# SCH_MagControl_Sheet2.net
KiCad netlist of a schematic drawn in Altium Designer
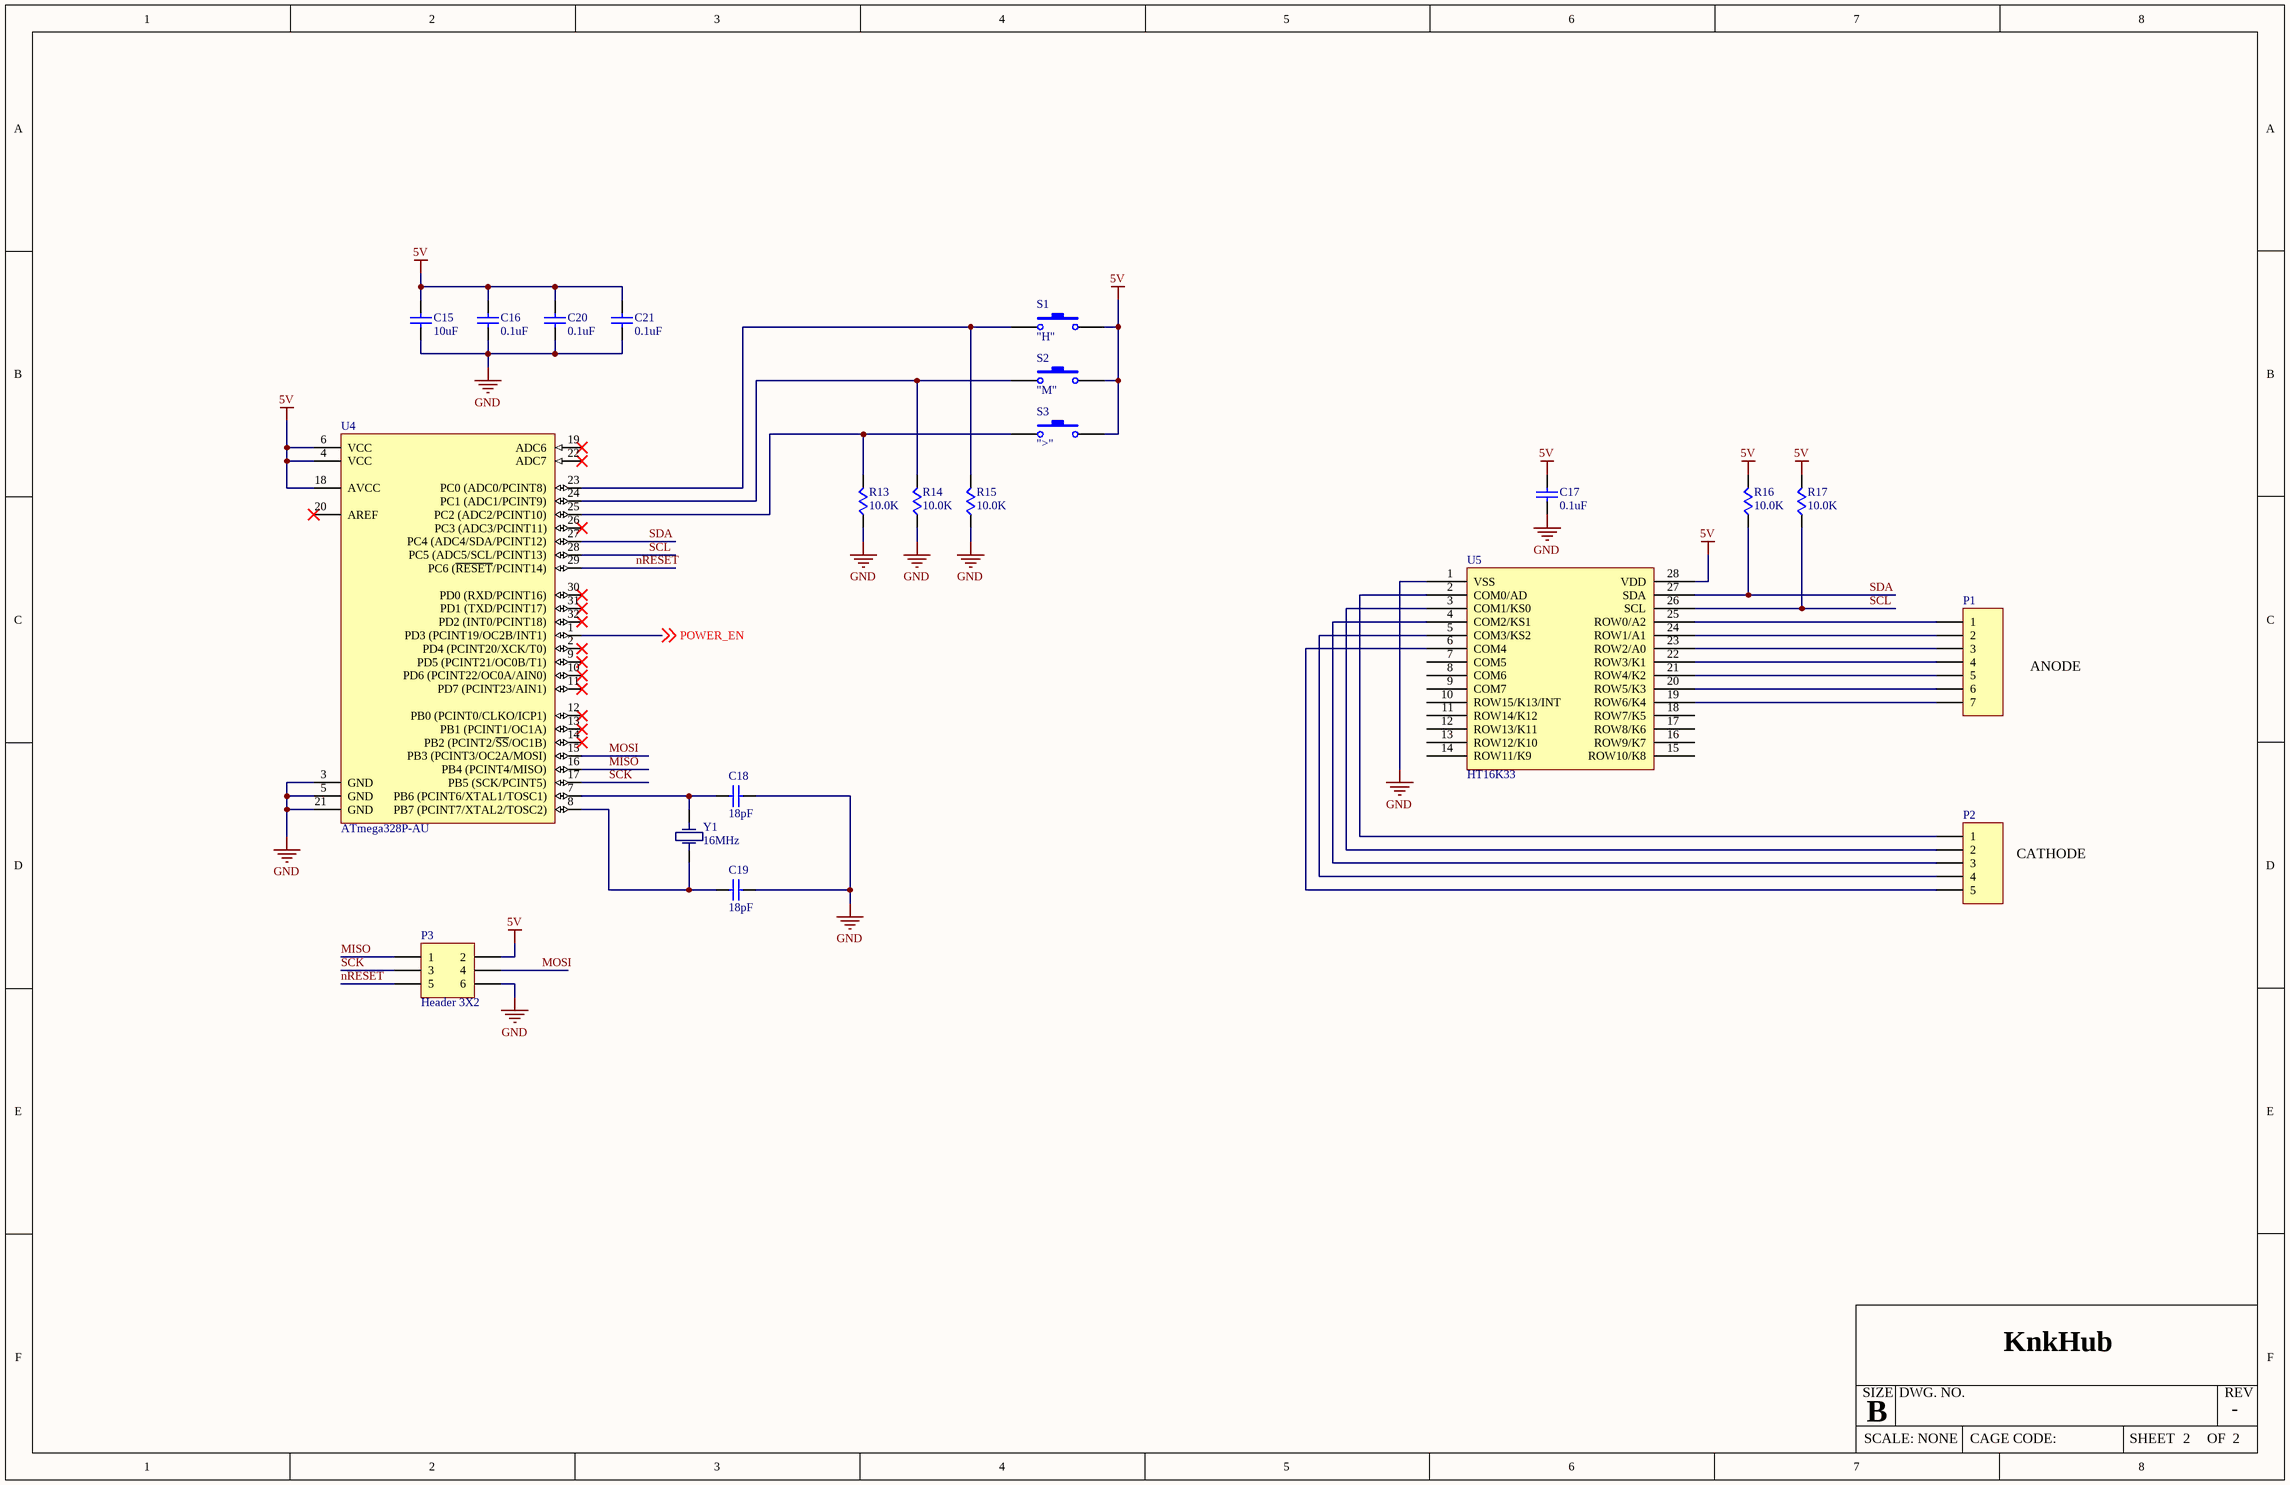
[diagram p0: SCH_MagControl_Sheet2.SchDoc]

(export (version "E")
  (design (tool "Eeschema 10.0.6"))
  (components
    (comp (ref "C15")
      (value "10uF")
      (footprint "CAPC1608L")
      (description "Capacitor (SMD)")
      (fields (field (name "TOLERANCE") "20%") (field (name "VOLTAGE") "6.3V"))
      (libsource (lib "MAST_Library") (part "Cap Semi"))
    )
    (comp (ref "C16")
      (value "0.1uF")
      (footprint "CAPC1005L")
      (description "Capacitor (SMD)")
      (fields (field (name "TOLERANCE") "20%"))
      (libsource (lib "MAST_Library") (part "Cap Semi"))
    )
    (comp (ref "C17")
      (value "0.1uF")
      (footprint "CAPC1005L")
      (description "Capacitor (SMD)")
      (fields (field (name "TOLERANCE") "20%"))
      (libsource (lib "MAST_Library") (part "Cap Semi"))
    )
    (comp (ref "C18")
      (value "18pF")
      (footprint "CAPC1005L")
      (description "Capacitor (SMD)")
      (fields
        (field (name "TOLERANCE") "5%")
        (field (name "VOLTAGE") "50V")
        (field (name "PUBLISHER") "Altium Limited")
      )
      (libsource (lib "HCG_Library") (part "Cap Semi"))
    )
    (comp (ref "C19")
      (value "18pF")
      (footprint "CAPC1005L")
      (description "Capacitor (SMD)")
      (fields
        (field (name "TOLERANCE") "5%")
        (field (name "VOLTAGE") "50V")
        (field (name "PUBLISHER") "Altium Limited")
      )
      (libsource (lib "HCG_Library") (part "Cap Semi"))
    )
    (comp (ref "C20")
      (value "0.1uF")
      (footprint "CAPC1005L")
      (description "Capacitor (SMD)")
      (fields (field (name "TOLERANCE") "20%"))
      (libsource (lib "MAST_Library") (part "Cap Semi"))
    )
    (comp (ref "C21")
      (value "0.1uF")
      (footprint "CAPC1005L")
      (description "Capacitor (SMD)")
      (fields (field (name "TOLERANCE") "20%"))
      (libsource (lib "MAST_Library") (part "Cap Semi"))
    )
    (comp (ref "P1")
      (value "~")
      (footprint "HDR1X7")
      (description "Header, 7-Pin")
      (fields (field (name "PUBLISHER") "Altium Limited"))
      (libsource (lib "Miscellaneous Connectors") (part "Header 7"))
    )
    (comp (ref "P2")
      (value "~")
      (footprint "HDR1X5")
      (description "Header, 5-Pin")
      (fields (field (name "PUBLISHER") "Altium Limited"))
      (libsource (lib "Miscellaneous Connectors") (part "Header 5"))
    )
    (comp (ref "P3")
      (value "Header 3X2")
      (footprint "HDR2X3")
      (description "Header, 3-Pin, Dual row")
      (fields (field (name "PUBLISHER") "Altium Limited"))
      (libsource (lib "Miscellaneous Connectors") (part "Header 3X2"))
    )
    (comp (ref "R13")
      (value "10.0K")
      (footprint "RESC1005N")
      (description "RES 10.0K OHM 1/10W 1% 0402 SMD")
      (fields (field (name "TOLERANCE") "1%"))
      (libsource (lib "MAST_Library") (part "R"))
    )
    (comp (ref "R14")
      (value "10.0K")
      (footprint "RESC1005N")
      (description "RES 10.0K OHM 1/10W 1% 0402 SMD")
      (fields (field (name "TOLERANCE") "1%"))
      (libsource (lib "MAST_Library") (part "R"))
    )
    (comp (ref "R15")
      (value "10.0K")
      (footprint "RESC1005N")
      (description "RES 10.0K OHM 1/10W 1% 0402 SMD")
      (fields (field (name "TOLERANCE") "1%"))
      (libsource (lib "MAST_Library") (part "R"))
    )
    (comp (ref "R16")
      (value "10.0K")
      (footprint "RESC1005N")
      (description "RES 10.0K OHM 1/10W 1% 0402 SMD")
      (fields (field (name "TOLERANCE") "1%"))
      (libsource (lib "MAST_Library") (part "R"))
    )
    (comp (ref "R17")
      (value "10.0K")
      (footprint "RESC1005N")
      (description "RES 10.0K OHM 1/10W 1% 0402 SMD")
      (fields (field (name "TOLERANCE") "1%"))
      (libsource (lib "MAST_Library") (part "R"))
    )
    (comp (ref "S1")
      (value "\"H\"")
      (footprint "SPST-2")
      (description "Switch")
      (fields (field (name "PUBLISHER") "Altium Limited"))
      (libsource (lib "Miscellaneous Devices") (part "SW-PB"))
    )
    (comp (ref "S2")
      (value "\"M\"")
      (footprint "SPST-2")
      (description "Switch")
      (fields (field (name "PUBLISHER") "Altium Limited"))
      (libsource (lib "Miscellaneous Devices") (part "SW-PB"))
    )
    (comp (ref "S3")
      (value "\">\"")
      (footprint "SPST-2")
      (description "Switch")
      (fields (field (name "PUBLISHER") "Altium Limited"))
      (libsource (lib "Miscellaneous Devices") (part "SW-PB"))
    )
    (comp (ref "U4")
      (value "ATmega328P-AU")
      (footprint "32A_L")
      (libsource (lib "Altium Content Vault") (part "MC-8B-ATM48-SQ32"))
    )
    (comp (ref "U5")
      (value "HT16K33")
      (footprint "SOP127P1030X264-28N")
      (description "LED Matrix Driver")
      (libsource (lib "HCG_Library") (part "HT16K33_28"))
    )
    (comp (ref "Y1")
      (value "16MHz")
      (footprint "CSM-3X")
      (description "CRYSTAL")
      (fields (field (name "TOLERANCE") "30ppm"))
      (libsource (lib "HCG_Library") (part "CRYSTAL"))
    )
  )
  (nets
    (net (code "1") (name "/MISO") (class "Default")
      (node (ref "P3") (pin "1") (pinfunction "1_1") (pintype "passive"))
      (node (ref "U4") (pin "16") (pinfunction "PB4_(PCINT4/MISO)_16") (pintype "bidirectional"))
    )
    (net (code "2") (name "/MOSI") (class "Default")
      (node (ref "P3") (pin "4") (pinfunction "4_4") (pintype "passive"))
      (node (ref "U4") (pin "15") (pinfunction "PB3_(PCINT3/OC2A/MOSI)_15") (pintype "bidirectional"))
    )
    (net (code "3") (name "/SCK") (class "Default")
      (node (ref "P3") (pin "3") (pinfunction "3_3") (pintype "passive"))
      (node (ref "U4") (pin "17") (pinfunction "PB5_(SCK/PCINT5)_17") (pintype "bidirectional"))
    )
    (net (code "4") (name "/SCL") (class "Default")
      (node (ref "R17") (pin "1") (pinfunction "1_1") (pintype "passive"))
      (node (ref "U4") (pin "28") (pinfunction "PC5_(ADC5/SCL/PCINT13)_28") (pintype "bidirectional"))
      (node (ref "U5") (pin "26") (pinfunction "SCL_26") (pintype "passive"))
    )
    (net (code "5") (name "/SDA") (class "Default")
      (node (ref "R16") (pin "1") (pinfunction "1_1") (pintype "passive"))
      (node (ref "U4") (pin "27") (pinfunction "PC4_(ADC4/SDA/PCINT12)_27") (pintype "bidirectional"))
      (node (ref "U5") (pin "27") (pinfunction "SDA_27") (pintype "passive"))
    )
    (net (code "6") (name "/nRESET") (class "Default")
      (node (ref "P3") (pin "5") (pinfunction "5_5") (pintype "passive"))
      (node (ref "U4") (pin "29") (pinfunction "PC6_(~{RESET}/PCINT14)_29") (pintype "bidirectional"))
    )
    (net (code "7") (name "5V") (class "Default")
      (node (ref "C15") (pin "2") (pinfunction "2_2") (pintype "passive"))
      (node (ref "C16") (pin "2") (pinfunction "2_2") (pintype "passive"))
      (node (ref "C17") (pin "2") (pinfunction "2_2") (pintype "passive"))
      (node (ref "C20") (pin "2") (pinfunction "2_2") (pintype "passive"))
      (node (ref "C21") (pin "2") (pinfunction "2_2") (pintype "passive"))
      (node (ref "P3") (pin "2") (pinfunction "2_2") (pintype "passive"))
      (node (ref "R16") (pin "2") (pinfunction "2_2") (pintype "passive"))
      (node (ref "R17") (pin "2") (pinfunction "2_2") (pintype "passive"))
      (node (ref "S1") (pin "2") (pinfunction "2_2") (pintype "passive"))
      (node (ref "S2") (pin "2") (pinfunction "2_2") (pintype "passive"))
      (node (ref "S3") (pin "2") (pinfunction "2_2") (pintype "passive"))
      (node (ref "U4") (pin "18") (pinfunction "AVCC_18") (pintype "power_in"))
      (node (ref "U4") (pin "4") (pinfunction "VCC_4") (pintype "power_in"))
      (node (ref "U4") (pin "6") (pinfunction "VCC_6") (pintype "power_in"))
      (node (ref "U5") (pin "28") (pinfunction "VDD_28") (pintype "passive"))
    )
    (net (code "8") (name "GND") (class "Default")
      (node (ref "C15") (pin "1") (pinfunction "1_1") (pintype "passive"))
      (node (ref "C16") (pin "1") (pinfunction "1_1") (pintype "passive"))
      (node (ref "C17") (pin "1") (pinfunction "1_1") (pintype "passive"))
      (node (ref "C18") (pin "1") (pinfunction "1_1") (pintype "passive"))
      (node (ref "C19") (pin "1") (pinfunction "1_1") (pintype "passive"))
      (node (ref "C20") (pin "1") (pinfunction "1_1") (pintype "passive"))
      (node (ref "C21") (pin "1") (pinfunction "1_1") (pintype "passive"))
      (node (ref "P3") (pin "6") (pinfunction "6_6") (pintype "passive"))
      (node (ref "R13") (pin "1") (pinfunction "1_1") (pintype "passive"))
      (node (ref "R14") (pin "1") (pinfunction "1_1") (pintype "passive"))
      (node (ref "R15") (pin "1") (pinfunction "1_1") (pintype "passive"))
      (node (ref "U4") (pin "21") (pinfunction "GND_21") (pintype "power_in"))
      (node (ref "U4") (pin "3") (pinfunction "GND_3") (pintype "power_in"))
      (node (ref "U4") (pin "5") (pinfunction "GND_5") (pintype "power_in"))
      (node (ref "U5") (pin "1") (pinfunction "VSS_1") (pintype "passive"))
    )
    (net (code "9") (name "Net-(U4-PB6_(PCINT6{slash}XTAL1{slash}TOSC1))") (class "Default")
      (node (ref "C18") (pin "2") (pinfunction "2_2") (pintype "passive"))
      (node (ref "U4") (pin "7") (pinfunction "PB6_(PCINT6/XTAL1/TOSC1)_7") (pintype "bidirectional"))
      (node (ref "Y1") (pin "1") (pinfunction "CI_1") (pintype "passive"))
    )
    (net (code "10") (name "Net-(U4-PB7_(PCINT7{slash}XTAL2{slash}TOSC2))") (class "Default")
      (node (ref "C19") (pin "2") (pinfunction "2_2") (pintype "passive"))
      (node (ref "U4") (pin "8") (pinfunction "PB7_(PCINT7/XTAL2/TOSC2)_8") (pintype "bidirectional"))
      (node (ref "Y1") (pin "2") (pinfunction "CO_2") (pintype "passive"))
    )
    (net (code "11") (name "Net-(U4-PC0_(ADC0{slash}PCINT8))") (class "Default")
      (node (ref "R15") (pin "2") (pinfunction "2_2") (pintype "passive"))
      (node (ref "S1") (pin "1") (pinfunction "1_1") (pintype "passive"))
      (node (ref "U4") (pin "23") (pinfunction "PC0_(ADC0/PCINT8)_23") (pintype "bidirectional"))
    )
    (net (code "12") (name "Net-(U4-PC1_(ADC1{slash}PCINT9))") (class "Default")
      (node (ref "R14") (pin "2") (pinfunction "2_2") (pintype "passive"))
      (node (ref "S2") (pin "1") (pinfunction "1_1") (pintype "passive"))
      (node (ref "U4") (pin "24") (pinfunction "PC1_(ADC1/PCINT9)_24") (pintype "bidirectional"))
    )
    (net (code "13") (name "Net-(U4-PC2_(ADC2{slash}PCINT10))") (class "Default")
      (node (ref "R13") (pin "2") (pinfunction "2_2") (pintype "passive"))
      (node (ref "S3") (pin "1") (pinfunction "1_1") (pintype "passive"))
      (node (ref "U4") (pin "25") (pinfunction "PC2_(ADC2/PCINT10)_25") (pintype "bidirectional"))
    )
    (net (code "14") (name "Net-(U5-COM0{slash}AD)") (class "Default")
      (node (ref "P2") (pin "1") (pinfunction "1_1") (pintype "passive"))
      (node (ref "U5") (pin "2") (pinfunction "COM0/AD_2") (pintype "passive"))
    )
    (net (code "15") (name "Net-(U5-COM1{slash}KS0)") (class "Default")
      (node (ref "P2") (pin "2") (pinfunction "2_2") (pintype "passive"))
      (node (ref "U5") (pin "3") (pinfunction "COM1/KS0_3") (pintype "passive"))
    )
    (net (code "16") (name "Net-(U5-COM2{slash}KS1)") (class "Default")
      (node (ref "P2") (pin "3") (pinfunction "3_3") (pintype "passive"))
      (node (ref "U5") (pin "4") (pinfunction "COM2/KS1_4") (pintype "passive"))
    )
    (net (code "17") (name "Net-(U5-COM3{slash}KS2)") (class "Default")
      (node (ref "P2") (pin "4") (pinfunction "4_4") (pintype "passive"))
      (node (ref "U5") (pin "5") (pinfunction "COM3/KS2_5") (pintype "passive"))
    )
    (net (code "18") (name "Net-(U5-COM4)") (class "Default")
      (node (ref "P2") (pin "5") (pinfunction "5_5") (pintype "passive"))
      (node (ref "U5") (pin "6") (pinfunction "COM4_6") (pintype "passive"))
    )
    (net (code "19") (name "Net-(U5-ROW0{slash}A2)") (class "Default")
      (node (ref "P1") (pin "1") (pinfunction "1_1") (pintype "passive"))
      (node (ref "U5") (pin "25") (pinfunction "ROW0/A2_25") (pintype "passive"))
    )
    (net (code "20") (name "Net-(U5-ROW1{slash}A1)") (class "Default")
      (node (ref "P1") (pin "2") (pinfunction "2_2") (pintype "passive"))
      (node (ref "U5") (pin "24") (pinfunction "ROW1/A1_24") (pintype "passive"))
    )
    (net (code "21") (name "Net-(U5-ROW2{slash}A0)") (class "Default")
      (node (ref "P1") (pin "3") (pinfunction "3_3") (pintype "passive"))
      (node (ref "U5") (pin "23") (pinfunction "ROW2/A0_23") (pintype "passive"))
    )
    (net (code "22") (name "Net-(U5-ROW3{slash}K1)") (class "Default")
      (node (ref "P1") (pin "4") (pinfunction "4_4") (pintype "passive"))
      (node (ref "U5") (pin "22") (pinfunction "ROW3/K1_22") (pintype "passive"))
    )
    (net (code "23") (name "Net-(U5-ROW4{slash}K2)") (class "Default")
      (node (ref "P1") (pin "5") (pinfunction "5_5") (pintype "passive"))
      (node (ref "U5") (pin "21") (pinfunction "ROW4/K2_21") (pintype "passive"))
    )
    (net (code "24") (name "Net-(U5-ROW5{slash}K3)") (class "Default")
      (node (ref "P1") (pin "6") (pinfunction "6_6") (pintype "passive"))
      (node (ref "U5") (pin "20") (pinfunction "ROW5/K3_20") (pintype "passive"))
    )
    (net (code "25") (name "Net-(U5-ROW6{slash}K4)") (class "Default")
      (node (ref "P1") (pin "7") (pinfunction "7_7") (pintype "passive"))
      (node (ref "U5") (pin "19") (pinfunction "ROW6/K4_19") (pintype "passive"))
    )
    (net (code "26") (name "POWER_EN") (class "Default")
      (node (ref "U4") (pin "1") (pinfunction "PD3_(PCINT19/OC2B/INT1)_1") (pintype "bidirectional"))
    )
    (net (code "27") (name "unconnected-(U4-ADC6-Pad19)") (class "Default")
      (node (ref "U4") (pin "19") (pinfunction "ADC6_19") (pintype "input+no_connect"))
    )
    (net (code "28") (name "unconnected-(U4-ADC7-Pad22)") (class "Default")
      (node (ref "U4") (pin "22") (pinfunction "ADC7_22") (pintype "input+no_connect"))
    )
    (net (code "29") (name "unconnected-(U4-AREF-Pad20)") (class "Default")
      (node (ref "U4") (pin "20") (pinfunction "AREF_20") (pintype "passive+no_connect"))
    )
    (net (code "30") (name "unconnected-(U4-PB0_(PCINT0{slash}CLKO{slash}ICP1)-Pad12)") (class "Default")
      (node (ref "U4") (pin "12") (pinfunction "PB0_(PCINT0/CLKO/ICP1)_12") (pintype "bidirectional+no_connect"))
    )
    (net (code "31") (name "unconnected-(U4-PB1_(PCINT1{slash}OC1A)-Pad13)") (class "Default")
      (node (ref "U4") (pin "13") (pinfunction "PB1_(PCINT1/OC1A)_13") (pintype "bidirectional+no_connect"))
    )
    (net (code "32") (name "unconnected-(U4-PB2_(PCINT2{slash}~{SS}{slash}OC1B)-Pad14)") (class "Default")
      (node (ref "U4") (pin "14") (pinfunction "PB2_(PCINT2/~{SS}/OC1B)_14") (pintype "bidirectional+no_connect"))
    )
    (net (code "33") (name "unconnected-(U4-PC3_(ADC3{slash}PCINT11)-Pad26)") (class "Default")
      (node (ref "U4") (pin "26") (pinfunction "PC3_(ADC3/PCINT11)_26") (pintype "bidirectional+no_connect"))
    )
    (net (code "34") (name "unconnected-(U4-PD0_(RXD{slash}PCINT16)-Pad30)") (class "Default")
      (node (ref "U4") (pin "30") (pinfunction "PD0_(RXD/PCINT16)_30") (pintype "bidirectional+no_connect"))
    )
    (net (code "35") (name "unconnected-(U4-PD1_(TXD{slash}PCINT17)-Pad31)") (class "Default")
      (node (ref "U4") (pin "31") (pinfunction "PD1_(TXD/PCINT17)_31") (pintype "bidirectional+no_connect"))
    )
    (net (code "36") (name "unconnected-(U4-PD2_(INT0{slash}PCINT18)-Pad32)") (class "Default")
      (node (ref "U4") (pin "32") (pinfunction "PD2_(INT0/PCINT18)_32") (pintype "bidirectional+no_connect"))
    )
    (net (code "37") (name "unconnected-(U4-PD4_(PCINT20{slash}XCK{slash}T0)-Pad2)") (class "Default")
      (node (ref "U4") (pin "2") (pinfunction "PD4_(PCINT20/XCK/T0)_2") (pintype "bidirectional+no_connect"))
    )
    (net (code "38") (name "unconnected-(U4-PD5_(PCINT21{slash}OC0B{slash}T1)-Pad9)") (class "Default")
      (node (ref "U4") (pin "9") (pinfunction "PD5_(PCINT21/OC0B/T1)_9") (pintype "bidirectional+no_connect"))
    )
    (net (code "39") (name "unconnected-(U4-PD6_(PCINT22{slash}OC0A{slash}AIN0)-Pad10)") (class "Default")
      (node (ref "U4") (pin "10") (pinfunction "PD6_(PCINT22/OC0A/AIN0)_10") (pintype "bidirectional+no_connect"))
    )
    (net (code "40") (name "unconnected-(U4-PD7_(PCINT23{slash}AIN1)-Pad11)") (class "Default")
      (node (ref "U4") (pin "11") (pinfunction "PD7_(PCINT23/AIN1)_11") (pintype "bidirectional+no_connect"))
    )
    (net (code "41") (name "unconnected-(U5-COM5-Pad7)") (class "Default")
      (node (ref "U5") (pin "7") (pinfunction "COM5_7") (pintype "passive"))
    )
    (net (code "42") (name "unconnected-(U5-COM6-Pad8)") (class "Default")
      (node (ref "U5") (pin "8") (pinfunction "COM6_8") (pintype "passive"))
    )
    (net (code "43") (name "unconnected-(U5-COM7-Pad9)") (class "Default")
      (node (ref "U5") (pin "9") (pinfunction "COM7_9") (pintype "passive"))
    )
    (net (code "44") (name "unconnected-(U5-ROW7{slash}K5-Pad18)") (class "Default")
      (node (ref "U5") (pin "18") (pinfunction "ROW7/K5_18") (pintype "passive"))
    )
    (net (code "45") (name "unconnected-(U5-ROW8{slash}K6-Pad17)") (class "Default")
      (node (ref "U5") (pin "17") (pinfunction "ROW8/K6_17") (pintype "passive"))
    )
    (net (code "46") (name "unconnected-(U5-ROW9{slash}K7-Pad16)") (class "Default")
      (node (ref "U5") (pin "16") (pinfunction "ROW9/K7_16") (pintype "passive"))
    )
    (net (code "47") (name "unconnected-(U5-ROW10{slash}K8-Pad15)") (class "Default")
      (node (ref "U5") (pin "15") (pinfunction "ROW10/K8_15") (pintype "passive"))
    )
    (net (code "48") (name "unconnected-(U5-ROW11{slash}K9-Pad14)") (class "Default")
      (node (ref "U5") (pin "14") (pinfunction "ROW11/K9_14") (pintype "passive"))
    )
    (net (code "49") (name "unconnected-(U5-ROW12{slash}K10-Pad13)") (class "Default")
      (node (ref "U5") (pin "13") (pinfunction "ROW12/K10_13") (pintype "passive"))
    )
    (net (code "50") (name "unconnected-(U5-ROW13{slash}K11-Pad12)") (class "Default")
      (node (ref "U5") (pin "12") (pinfunction "ROW13/K11_12") (pintype "passive"))
    )
    (net (code "51") (name "unconnected-(U5-ROW14{slash}K12-Pad11)") (class "Default")
      (node (ref "U5") (pin "11") (pinfunction "ROW14/K12_11") (pintype "passive"))
    )
    (net (code "52") (name "unconnected-(U5-ROW15{slash}K13{slash}INT-Pad10)") (class "Default")
      (node (ref "U5") (pin "10") (pinfunction "ROW15/K13/INT_10") (pintype "passive"))
    )
  )
)
